# Burpg_altimeter_v1.net
KiCad netlist of a schematic drawn in EAGLE
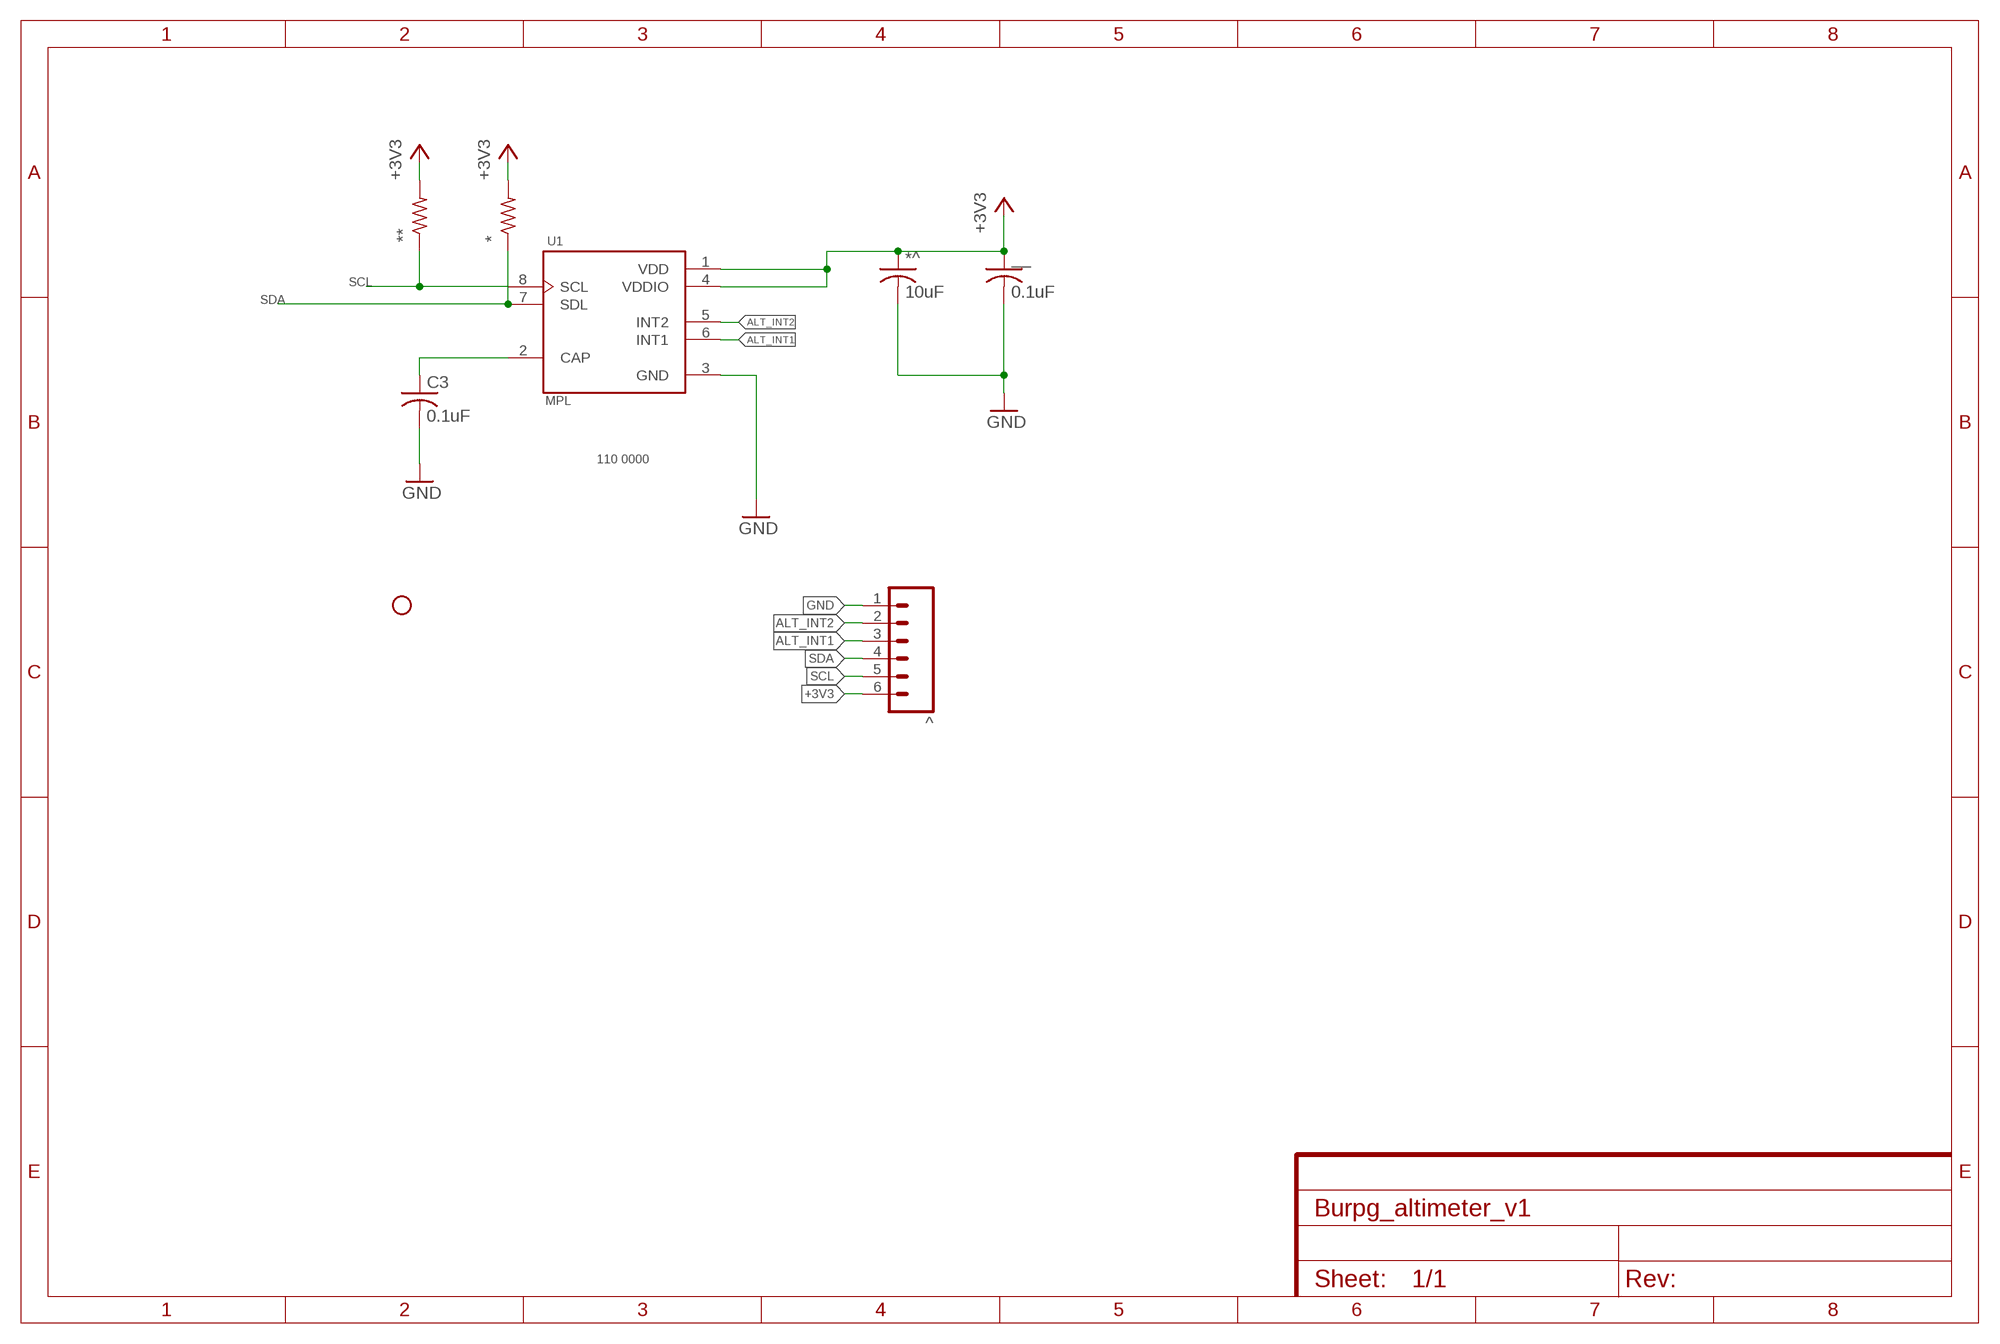
[diagram p0: schematic, sheet 1]

(export (version "E")
  (design (tool "Eeschema 10.0.6"))
  (components
    (comp (ref "*")
      (value "R-US_R0603")
      (footprint "eagle-import:R0603")
      (libsource (lib "eagle-import") (part "R-US_R0603"))
    )
    (comp (ref "**")
      (value "R-US_R0603")
      (footprint "eagle-import:R0603")
      (libsource (lib "eagle-import") (part "R-US_R0603"))
    )
    (comp (ref "*^")
      (value "10uF")
      (footprint "eagle-import:C0603K")
      (libsource (lib "eagle-import") (part "C-USC0603K"))
    )
    (comp (ref "C3")
      (value "0.1uF")
      (footprint "eagle-import:C0603K")
      (libsource (lib "eagle-import") (part "C-USC0603K"))
    )
    (comp (ref "U1")
      (value "MPL")
      (footprint "eagle-import:PSON125P300X500X120-8N")
      (fields (field (name "MF") "NXP Semiconductors") (field (name "MP") "MPL3115A2"))
      (libsource (lib "eagle-import") (part "MPL3115A2"))
    )
    (comp (ref "^")
      (value "M06SILK_FEMALE_PTH")
      (footprint "eagle-import:1X06")
      (libsource (lib "eagle-import") (part "M06SILK_FEMALE_PTH"))
    )
    (comp (ref "_")
      (value "#4_philip")
      (footprint "eagle-import:STAND-OFF")
      (libsource (lib "eagle-import") (part "STAND-OFF"))
    )
    (comp (ref "__")
      (value "0.1uF")
      (footprint "eagle-import:C0603K")
      (libsource (lib "eagle-import") (part "C-USC0603K"))
    )
  )
  (nets
    (net (code "1") (name "+3V3") (class "Default")
      (node (ref "*") (pin "2") (pinfunction "2_2") (pintype "passive"))
      (node (ref "**") (pin "2") (pinfunction "2_2") (pintype "passive"))
      (node (ref "*^") (pin "1") (pinfunction "1_1") (pintype "passive"))
      (node (ref "U1") (pin "1") (pinfunction "VDD_1") (pintype "power_in"))
      (node (ref "U1") (pin "4") (pinfunction "VDDIO_4") (pintype "power_in"))
      (node (ref "^") (pin "6") (pinfunction "6_6") (pintype "passive"))
      (node (ref "__") (pin "1") (pinfunction "1_1") (pintype "passive"))
    )
    (net (code "2") (name "ALT_INT1") (class "Default")
      (node (ref "U1") (pin "6") (pinfunction "INT1_6") (pintype "output"))
      (node (ref "^") (pin "3") (pinfunction "3_3") (pintype "passive"))
    )
    (net (code "3") (name "ALT_INT2") (class "Default")
      (node (ref "U1") (pin "5") (pinfunction "INT2_5") (pintype "output"))
      (node (ref "^") (pin "2") (pinfunction "2_2") (pintype "passive"))
    )
    (net (code "4") (name "GND") (class "Default")
      (node (ref "*^") (pin "2") (pinfunction "2_2") (pintype "passive"))
      (node (ref "C3") (pin "2") (pinfunction "2_2") (pintype "passive"))
      (node (ref "U1") (pin "3") (pinfunction "GND_3") (pintype "power_in"))
      (node (ref "^") (pin "1") (pinfunction "1_1") (pintype "passive"))
      (node (ref "__") (pin "2") (pinfunction "2_2") (pintype "passive"))
    )
    (net (code "5") (name "Net-(U1-CAP)") (class "Default")
      (node (ref "C3") (pin "1") (pinfunction "1_1") (pintype "passive"))
      (node (ref "U1") (pin "2") (pinfunction "CAP_2") (pintype "bidirectional"))
    )
    (net (code "6") (name "SCL") (class "Default")
      (node (ref "**") (pin "1") (pinfunction "1_1") (pintype "passive"))
      (node (ref "U1") (pin "8") (pinfunction "SCL_8") (pintype "input"))
      (node (ref "^") (pin "5") (pinfunction "5_5") (pintype "passive"))
    )
    (net (code "7") (name "SDA") (class "Default")
      (node (ref "*") (pin "1") (pinfunction "1_1") (pintype "passive"))
      (node (ref "U1") (pin "7") (pinfunction "SDL_7") (pintype "bidirectional"))
      (node (ref "^") (pin "4") (pinfunction "4_4") (pintype "passive"))
    )
  )
)
